# lab1_yarmak_usb_spi.net
KiCad netlist of a schematic drawn in Altium Designer
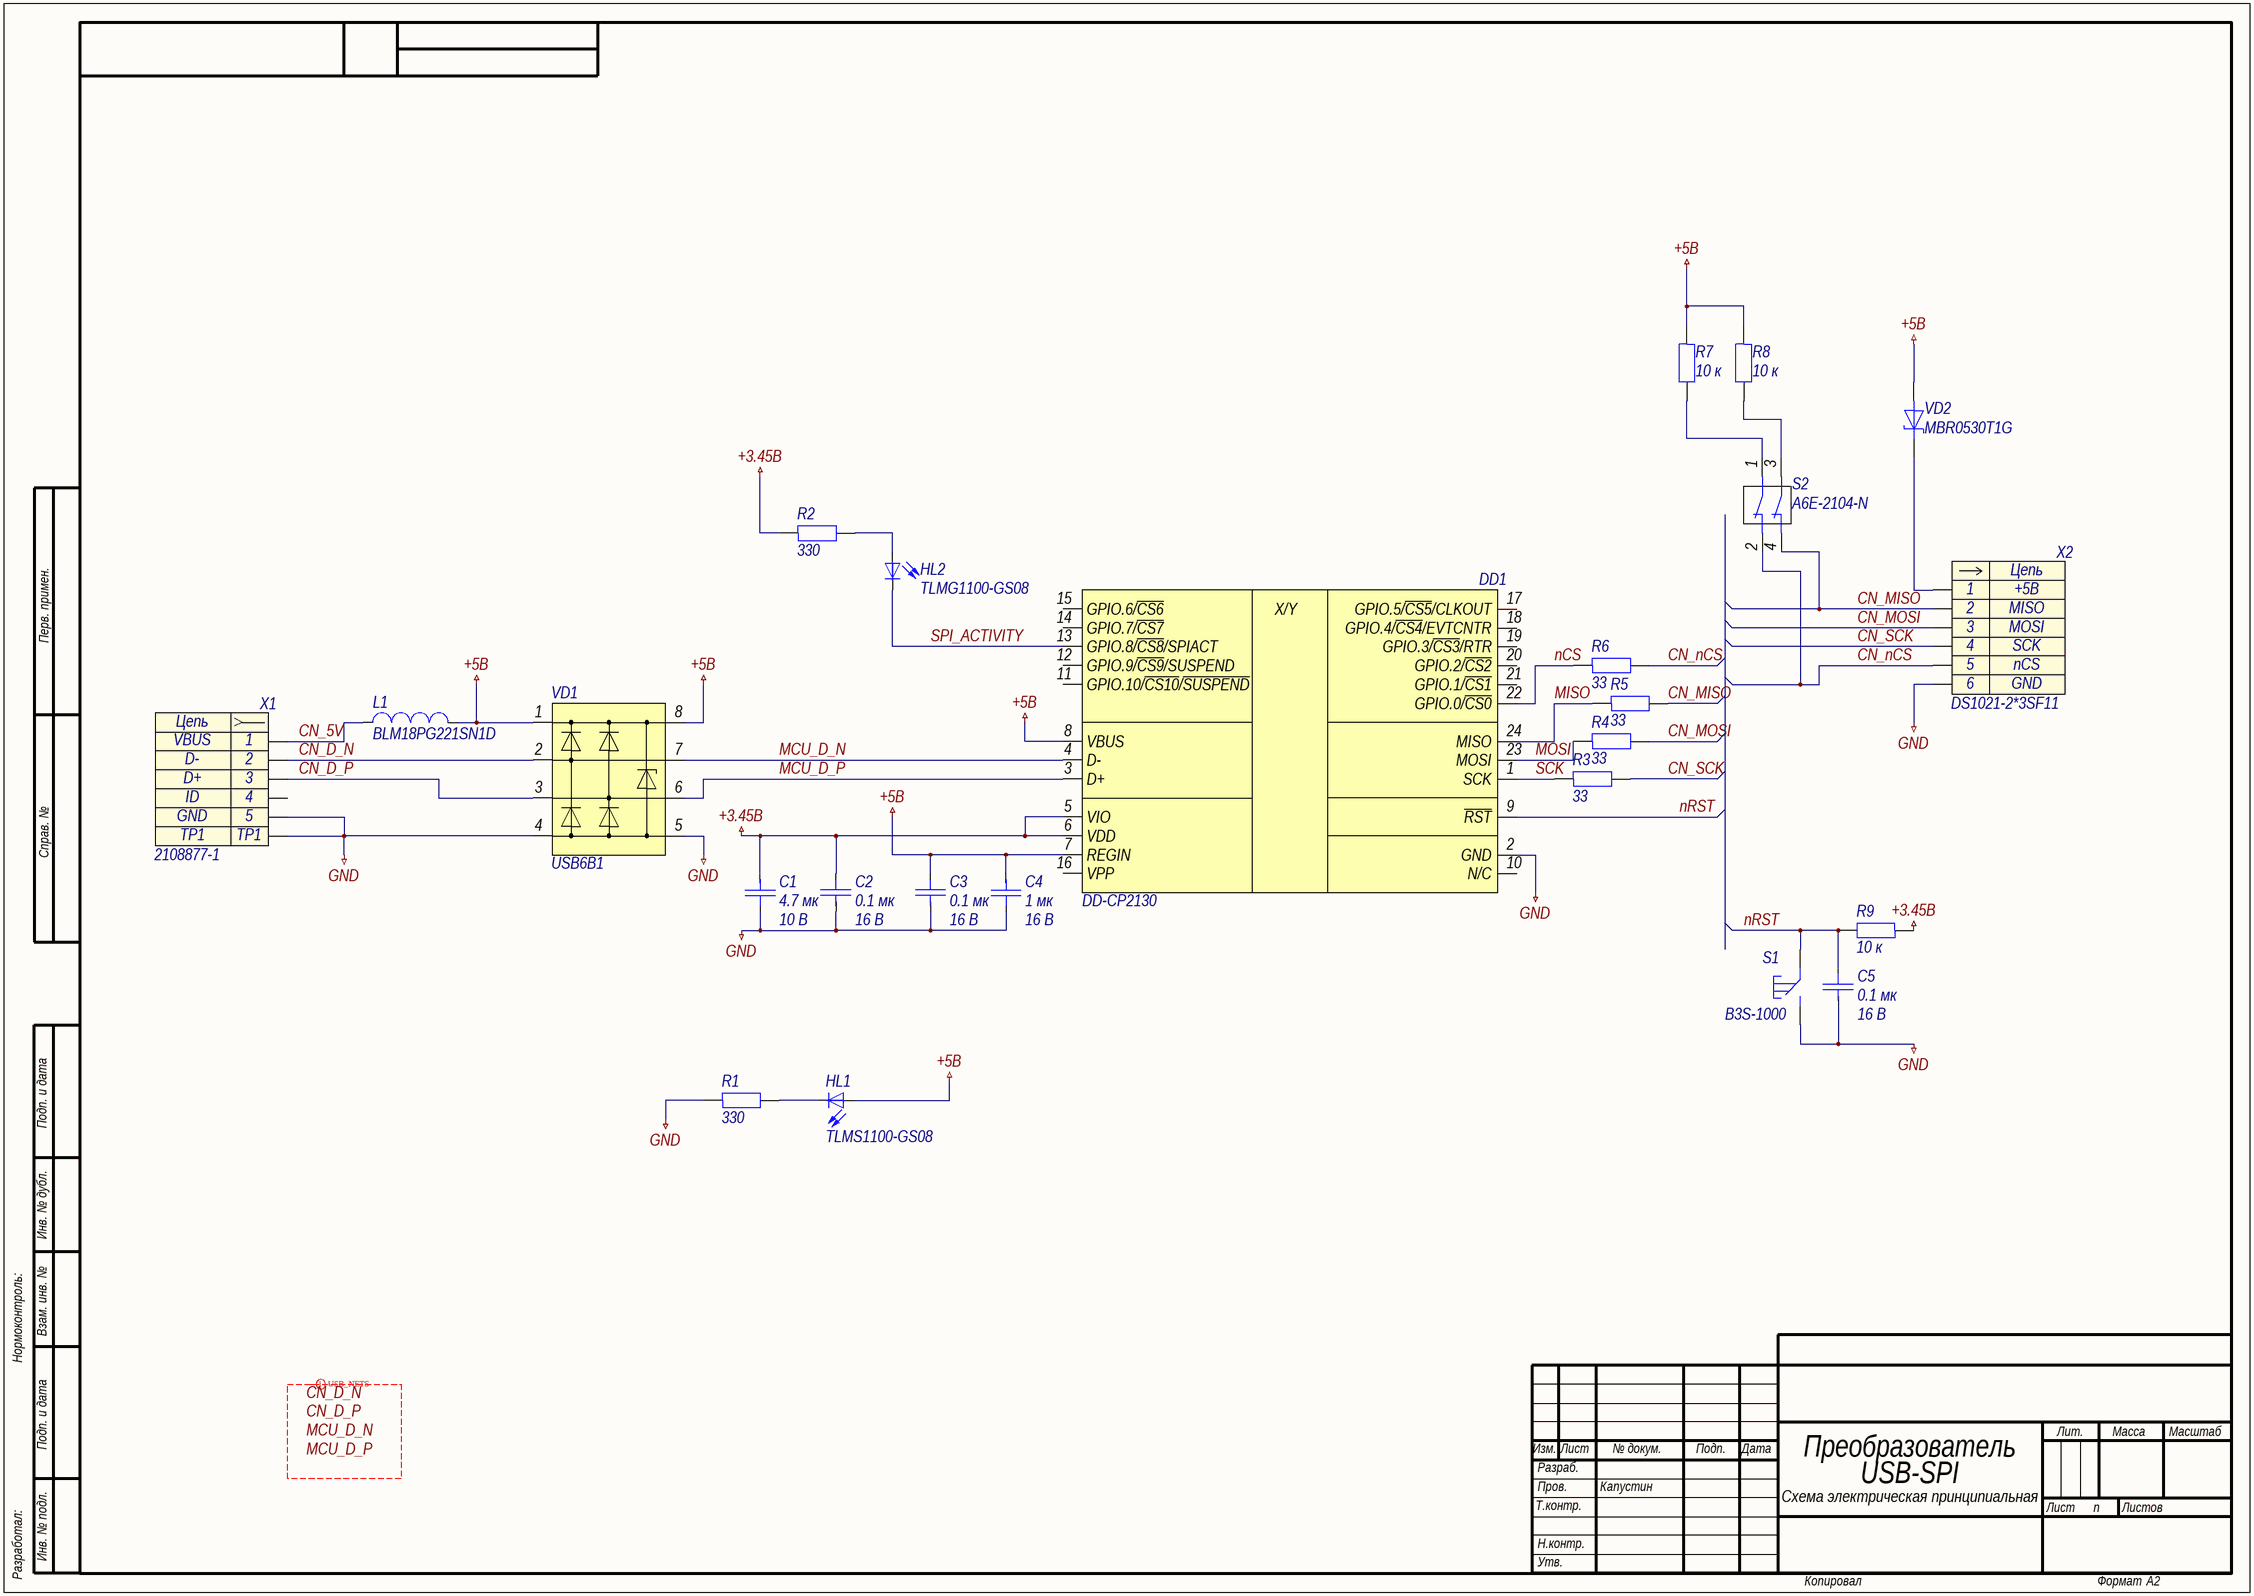
[diagram p0: lab1_yarmak_usb_spi.SchDoc]

(export (version "E")
  (design (tool "Eeschema 10.0.6"))
  (components
    (comp (ref "C1")
      (value "4.7 мк")
      (footprint "C0402")
      (description "=Описание")
      (fields (field (name "НАПРЯЖЕНИЕ") "10 В"))
      (libsource (lib "Database_Students") (part "cap"))
    )
    (comp (ref "C2")
      (value "0.1 мк")
      (footprint "C0402")
      (description "=Описание")
      (fields (field (name "НАПРЯЖЕНИЕ") "16 В"))
      (libsource (lib "Database_Students") (part "cap"))
    )
    (comp (ref "C3")
      (value "0.1 мк")
      (footprint "C0402")
      (description "=Описание")
      (fields (field (name "НАПРЯЖЕНИЕ") "16 В"))
      (libsource (lib "Database_Students") (part "cap"))
    )
    (comp (ref "C4")
      (value "1 мк")
      (footprint "C0402")
      (description "=Описание")
      (fields (field (name "НАПРЯЖЕНИЕ") "16 В"))
      (libsource (lib "Database_Students") (part "cap"))
    )
    (comp (ref "C5")
      (value "0.1 мк")
      (footprint "C0402")
      (description "=Описание")
      (fields (field (name "НАПРЯЖЕНИЕ") "16 В"))
      (libsource (lib "Database_Students") (part "cap"))
    )
    (comp (ref "DD1")
      (value "DD-CP2130")
      (footprint "CP2130")
      (description "=Описание")
      (libsource (lib "Database_Students") (part "DD-CP2130"))
    )
    (comp (ref "HL1")
      (value "TLMS1100-GS08")
      (footprint "LED")
      (description "=Описание")
      (libsource (lib "Database_Students") (part "led"))
    )
    (comp (ref "HL2")
      (value "TLMG1100-GS08")
      (footprint "LED_GREEN")
      (description "=Описание")
      (libsource (lib "Database_Students") (part "led"))
    )
    (comp (ref "L1")
      (value "BLM18PG221SN1D")
      (footprint "L0603")
      (description "=Описание")
      (libsource (lib "Database_Students") (part "L-bead"))
    )
    (comp (ref "R1")
      (value "330")
      (footprint "R0603")
      (description "=Описание")
      (libsource (lib "Database_Students") (part "R-0.063W"))
    )
    (comp (ref "R2")
      (value "330")
      (footprint "R0603")
      (description "=Описание")
      (libsource (lib "Database_Students") (part "R-0.063W"))
    )
    (comp (ref "R3")
      (value "33")
      (footprint "R0603")
      (description "=Описание")
      (libsource (lib "Database_Students") (part "R-0.063W"))
    )
    (comp (ref "R4")
      (value "33")
      (footprint "R0603")
      (description "=Описание")
      (libsource (lib "Database_Students") (part "R-0.063W"))
    )
    (comp (ref "R5")
      (value "33")
      (footprint "R0603")
      (description "=Описание")
      (libsource (lib "Database_Students") (part "R-0.063W"))
    )
    (comp (ref "R6")
      (value "33")
      (footprint "R0603")
      (description "=Описание")
      (libsource (lib "Database_Students") (part "R-0.063W"))
    )
    (comp (ref "R7")
      (value "10 к")
      (footprint "R0603")
      (description "=Описание")
      (libsource (lib "Database_Students") (part "R-0.063W"))
    )
    (comp (ref "R8")
      (value "10 к")
      (footprint "R0603")
      (description "=Описание")
      (libsource (lib "Database_Students") (part "R-0.063W"))
    )
    (comp (ref "R9")
      (value "10 к")
      (footprint "R0603")
      (description "=Описание")
      (libsource (lib "Database_Students") (part "R-0.063W"))
    )
    (comp (ref "S1")
      (value "B3S-1000")
      (footprint "BUTTON")
      (description "=Описание")
      (libsource (lib "Database_Students") (part "S-button"))
    )
    (comp (ref "S2")
      (value "A6E-2104-N")
      (footprint "A6E-2104-N")
      (description "=Описание")
      (libsource (lib "Database_Students") (part "switch"))
    )
    (comp (ref "VD1")
      (value "USB6B1")
      (footprint "SOIC-8-P127-490X390X175-L84X41")
      (description "=Описание")
      (libsource (lib "Database_Students") (part "USB6B1"))
    )
    (comp (ref "VD2")
      (value "MBR0530T1G")
      (footprint "SOD-123-368X160X135")
      (description "=Описание")
      (libsource (lib "Database_Students") (part "DIODE-SCHOTTKY"))
    )
    (comp (ref "X1")
      (value "2108877-1")
      (footprint "2108877-1")
      (description "=Описание")
      (libsource (lib "Database_Students") (part "MICRO_USB-B"))
    )
    (comp (ref "X2")
      (value "DS1021-2*3SF11")
      (footprint "PLS_2.54_2x3")
      (description "=Описание")
      (libsource (lib "Database_Students") (part "DS1021-2*3SF11"))
    )
  )
  (nets
    (net (code "1") (name "+3.45В") (class "Default")
      (node (ref "C1") (pin "2") (pinfunction "2_2") (pintype "passive"))
      (node (ref "C2") (pin "1") (pinfunction "1_1") (pintype "passive"))
      (node (ref "DD1") (pin "5") (pinfunction "VIO_5") (pintype "passive"))
      (node (ref "DD1") (pin "6") (pinfunction "VDD_6") (pintype "passive"))
      (node (ref "R2") (pin "1") (pinfunction "1_1") (pintype "passive"))
      (node (ref "R9") (pin "1") (pinfunction "1_1") (pintype "passive"))
    )
    (net (code "2") (name "+5В") (class "Default")
      (node (ref "C3") (pin "1") (pinfunction "1_1") (pintype "passive"))
      (node (ref "C4") (pin "2") (pinfunction "2_2") (pintype "passive"))
      (node (ref "DD1") (pin "7") (pinfunction "REGIN_7") (pintype "passive"))
      (node (ref "DD1") (pin "8") (pinfunction "VBUS_8") (pintype "passive"))
      (node (ref "HL1") (pin "1") (pinfunction "A_1") (pintype "passive"))
      (node (ref "L1") (pin "2") (pinfunction "2_2") (pintype "passive"))
      (node (ref "R7") (pin "1") (pinfunction "1_1") (pintype "passive"))
      (node (ref "R8") (pin "1") (pinfunction "1_1") (pintype "passive"))
      (node (ref "VD1") (pin "1") (pinfunction "1_1") (pintype "passive"))
      (node (ref "VD1") (pin "8") (pinfunction "8_8") (pintype "passive"))
      (node (ref "VD2") (pin "2") (pinfunction "2_2") (pintype "passive"))
    )
    (net (code "3") (name "/CN_5V") (class "Default")
      (node (ref "L1") (pin "1") (pinfunction "1_1") (pintype "passive"))
      (node (ref "X1") (pin "1") (pinfunction "1_1") (pintype "passive"))
    )
    (net (code "4") (name "/CN_D_N") (class "Default")
      (node (ref "VD1") (pin "2") (pinfunction "2_2") (pintype "passive"))
      (node (ref "X1") (pin "2") (pinfunction "2_2") (pintype "passive"))
    )
    (net (code "5") (name "/CN_D_P") (class "Default")
      (node (ref "VD1") (pin "3") (pinfunction "3_3") (pintype "passive"))
      (node (ref "X1") (pin "3") (pinfunction "3_3") (pintype "passive"))
    )
    (net (code "6") (name "/CN_MISO") (class "Default")
      (node (ref "R5") (pin "2") (pinfunction "2_2") (pintype "passive"))
      (node (ref "S2") (pin "4") (pinfunction "4_4") (pintype "passive"))
      (node (ref "X2") (pin "2") (pinfunction "2_2") (pintype "passive"))
    )
    (net (code "7") (name "/CN_MOSI") (class "Default")
      (node (ref "R4") (pin "2") (pinfunction "2_2") (pintype "passive"))
      (node (ref "X2") (pin "3") (pinfunction "3_3") (pintype "passive"))
    )
    (net (code "8") (name "/CN_SCK") (class "Default")
      (node (ref "R3") (pin "2") (pinfunction "2_2") (pintype "passive"))
      (node (ref "X2") (pin "4") (pinfunction "4_4") (pintype "passive"))
    )
    (net (code "9") (name "/CN_nCS") (class "Default")
      (node (ref "R6") (pin "2") (pinfunction "2_2") (pintype "passive"))
      (node (ref "S2") (pin "2") (pinfunction "2_2") (pintype "passive"))
      (node (ref "X2") (pin "5") (pinfunction "5_5") (pintype "passive"))
    )
    (net (code "10") (name "/MCU_D_N") (class "Default")
      (node (ref "DD1") (pin "4") (pinfunction "D-_4") (pintype "passive"))
      (node (ref "VD1") (pin "7") (pinfunction "7_7") (pintype "passive"))
    )
    (net (code "11") (name "/MCU_D_P") (class "Default")
      (node (ref "DD1") (pin "3") (pinfunction "D+_3") (pintype "passive"))
      (node (ref "VD1") (pin "6") (pinfunction "6_6") (pintype "passive"))
    )
    (net (code "12") (name "/MISO") (class "Default")
      (node (ref "DD1") (pin "24") (pinfunction "MISO_24") (pintype "passive"))
      (node (ref "R5") (pin "1") (pinfunction "1_1") (pintype "passive"))
    )
    (net (code "13") (name "/MOSI") (class "Default")
      (node (ref "DD1") (pin "23") (pinfunction "MOSI_23") (pintype "passive"))
      (node (ref "R4") (pin "1") (pinfunction "1_1") (pintype "passive"))
    )
    (net (code "14") (name "/SCK") (class "Default")
      (node (ref "DD1") (pin "1") (pinfunction "SCK_1") (pintype "passive"))
      (node (ref "R3") (pin "1") (pinfunction "1_1") (pintype "passive"))
    )
    (net (code "15") (name "/SPI_ACTIVITY") (class "Default")
      (node (ref "DD1") (pin "13") (pinfunction "GPIO.8/~{CS8}/SPIACT_13") (pintype "passive"))
      (node (ref "HL2") (pin "2") (pinfunction "K_2") (pintype "passive"))
    )
    (net (code "16") (name "/nCS") (class "Default")
      (node (ref "DD1") (pin "22") (pinfunction "GPIO.0/~{CS0}_22") (pintype "passive"))
      (node (ref "R6") (pin "1") (pinfunction "1_1") (pintype "passive"))
    )
    (net (code "17") (name "/nRST") (class "Default")
      (node (ref "C5") (pin "1") (pinfunction "1_1") (pintype "passive"))
      (node (ref "DD1") (pin "9") (pinfunction "~{RST}_9") (pintype "passive"))
      (node (ref "R9") (pin "2") (pinfunction "2_2") (pintype "passive"))
      (node (ref "S1") (pin "2") (pinfunction "2_2") (pintype "passive"))
    )
    (net (code "18") (name "GND") (class "Default")
      (node (ref "C1") (pin "1") (pinfunction "1_1") (pintype "passive"))
      (node (ref "C2") (pin "2") (pinfunction "2_2") (pintype "passive"))
      (node (ref "C3") (pin "2") (pinfunction "2_2") (pintype "passive"))
      (node (ref "C4") (pin "1") (pinfunction "1_1") (pintype "passive"))
      (node (ref "C5") (pin "2") (pinfunction "2_2") (pintype "passive"))
      (node (ref "DD1") (pin "2") (pinfunction "GND_2") (pintype "passive"))
      (node (ref "R1") (pin "1") (pinfunction "1_1") (pintype "passive"))
      (node (ref "VD1") (pin "4") (pinfunction "4_4") (pintype "passive"))
      (node (ref "VD1") (pin "5") (pinfunction "5_5") (pintype "passive"))
      (node (ref "X1") (pin "5") (pinfunction "5_5") (pintype "passive"))
      (node (ref "X1") (pin "TP1") (pinfunction "TP1_TP1") (pintype "passive"))
      (node (ref "X2") (pin "6") (pinfunction "6_6") (pintype "passive"))
    )
    (net (code "19") (name "Net-(HL1-K)") (class "Default")
      (node (ref "HL1") (pin "2") (pinfunction "K_2") (pintype "passive"))
      (node (ref "R1") (pin "2") (pinfunction "2_2") (pintype "passive"))
    )
    (net (code "20") (name "Net-(HL2-A)") (class "Default")
      (node (ref "HL2") (pin "1") (pinfunction "A_1") (pintype "passive"))
      (node (ref "R2") (pin "2") (pinfunction "2_2") (pintype "passive"))
    )
    (net (code "21") (name "Net-(R7-Pad2)") (class "Default")
      (node (ref "R7") (pin "2") (pinfunction "2_2") (pintype "passive"))
      (node (ref "S2") (pin "1") (pinfunction "1_1") (pintype "passive"))
    )
    (net (code "22") (name "Net-(R8-Pad2)") (class "Default")
      (node (ref "R8") (pin "2") (pinfunction "2_2") (pintype "passive"))
      (node (ref "S2") (pin "3") (pinfunction "3_3") (pintype "passive"))
    )
    (net (code "23") (name "Net-(VD2-Pad1)") (class "Default")
      (node (ref "VD2") (pin "1") (pinfunction "1_1") (pintype "passive"))
      (node (ref "X2") (pin "1") (pinfunction "1_1") (pintype "passive"))
    )
    (net (code "24") (name "unconnected-(DD1-GPIO.1{slash}~{CS1}-Pad21)") (class "Default")
      (node (ref "DD1") (pin "21") (pinfunction "GPIO.1/~{CS1}_21") (pintype "passive"))
    )
    (net (code "25") (name "unconnected-(DD1-GPIO.2{slash}~{CS2}-Pad20)") (class "Default")
      (node (ref "DD1") (pin "20") (pinfunction "GPIO.2/~{CS2}_20") (pintype "passive"))
    )
    (net (code "26") (name "unconnected-(DD1-GPIO.3{slash}~{CS3}{slash}RTR-Pad19)") (class "Default")
      (node (ref "DD1") (pin "19") (pinfunction "GPIO.3/~{CS3}/RTR_19") (pintype "passive"))
    )
    (net (code "27") (name "unconnected-(DD1-GPIO.4{slash}~{CS4}{slash}EVTCNTR-Pad18)") (class "Default")
      (node (ref "DD1") (pin "18") (pinfunction "GPIO.4/~{CS4}/EVTCNTR_18") (pintype "passive"))
    )
    (net (code "28") (name "unconnected-(DD1-GPIO.5{slash}~{CS5}{slash}CLKOUT-Pad17)") (class "Default")
      (node (ref "DD1") (pin "17") (pinfunction "GPIO.5/~{CS5}/CLKOUT_17") (pintype "passive"))
    )
    (net (code "29") (name "unconnected-(DD1-GPIO.6{slash}~{CS6}-Pad15)") (class "Default")
      (node (ref "DD1") (pin "15") (pinfunction "GPIO.6/~{CS6}_15") (pintype "passive"))
    )
    (net (code "30") (name "unconnected-(DD1-GPIO.7{slash}~{CS7}-Pad14)") (class "Default")
      (node (ref "DD1") (pin "14") (pinfunction "GPIO.7/~{CS7}_14") (pintype "passive"))
    )
    (net (code "31") (name "unconnected-(DD1-GPIO.9{slash}~{CS9}{slash}SUSPEND-Pad12)") (class "Default")
      (node (ref "DD1") (pin "12") (pinfunction "GPIO.9/~{CS9}/SUSPEND_12") (pintype "passive"))
    )
    (net (code "32") (name "unconnected-(DD1-GPIO.10{slash}~{CS10}{slash}~{SUSPEND}-Pad11)") (class "Default")
      (node (ref "DD1") (pin "11") (pinfunction "GPIO.10/~{CS10}/~{SUSPEND}_11") (pintype "passive"))
    )
    (net (code "33") (name "unconnected-(DD1-N{slash}C-Pad10)") (class "Default")
      (node (ref "DD1") (pin "10") (pinfunction "N/C_10") (pintype "passive"))
    )
    (net (code "34") (name "unconnected-(DD1-VPP-Pad16)") (class "Default")
      (node (ref "DD1") (pin "16") (pinfunction "VPP_16") (pintype "passive"))
    )
    (net (code "35") (name "unconnected-(S1-Pad1)") (class "Default")
      (node (ref "S1") (pin "1") (pinfunction "1_1") (pintype "passive"))
    )
    (net (code "36") (name "unconnected-(X1-Pad4)") (class "Default")
      (node (ref "X1") (pin "4") (pinfunction "4_4") (pintype "passive"))
    )
  )
)
